# arduino_uno_shield.net
KiCad netlist of a schematic drawn in EAGLE
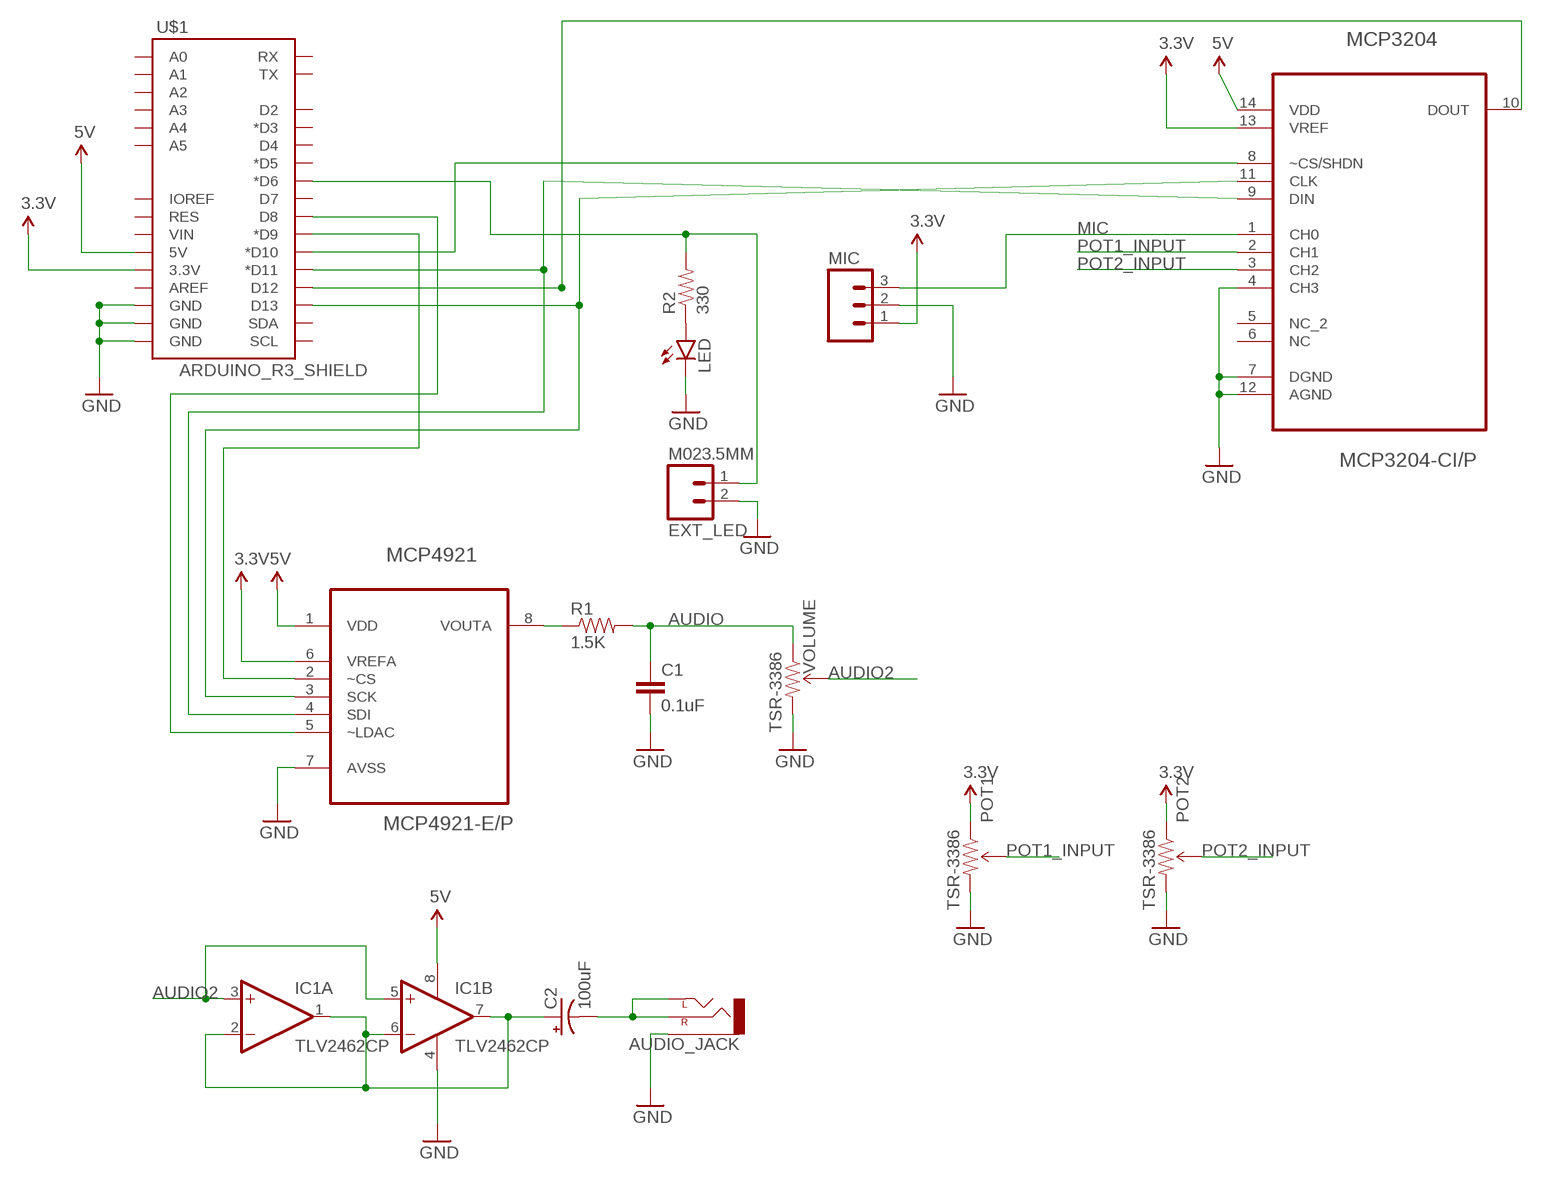
[diagram p0: schematic, sheet 1]

(export (version "E")
  (design (tool "Eeschema 10.0.6"))
  (components
    (comp (ref "AUDIO_JACK")
      (value "AUDIO-JACKPTH")
      (footprint "eagle-import:AUDIO-JACK")
      (libsource (lib "eagle-import") (part "AUDIO-JACKPTH"))
    )
    (comp (ref "C1")
      (value "0.1uF")
      (footprint "eagle-import:CAP-PTH-SMALL")
      (libsource (lib "eagle-import") (part "CAPPTH"))
    )
    (comp (ref "C2")
      (value "100uF")
      (footprint "eagle-import:CPOL-RADIAL-100UF-25V")
      (libsource (lib "eagle-import") (part "CAP_POLPTH1"))
    )
    (comp (ref "EXT_LED")
      (value "M023.5MM")
      (footprint "eagle-import:SCREWTERMINAL-3.5MM-2")
      (libsource (lib "eagle-import") (part "M023.5MM"))
    )
    (comp (ref "IC1")
      (value "TLV2462CP")
      (footprint "eagle-import:DIL08")
      (libsource (lib "eagle-import") (part "TL072P"))
    )
    (comp (ref "LED")
      (value "LED5MM")
      (footprint "eagle-import:LED5MM")
      (libsource (lib "eagle-import") (part "LED5MM"))
    )
    (comp (ref "MCP3204")
      (value "MCP3204-CI/P")
      (footprint "eagle-import:DIP254P762X432-14")
      (libsource (lib "eagle-import") (part "MCP3204-CI/P"))
    )
    (comp (ref "MCP4921")
      (value "MCP4921-E/P")
      (footprint "eagle-import:DIP254P762X432-8")
      (libsource (lib "eagle-import") (part "MCP4921-E/P"))
    )
    (comp (ref "MIC")
      (value "M03PTH")
      (footprint "eagle-import:1X03")
      (libsource (lib "eagle-import") (part "M03PTH"))
    )
    (comp (ref "POT1")
      (value "TSR-3386")
      (footprint "eagle-import:3386U")
      (libsource (lib "eagle-import") (part "TRIMPOT-PTH-KNOB"))
    )
    (comp (ref "POT2")
      (value "TSR-3386")
      (footprint "eagle-import:3386U")
      (libsource (lib "eagle-import") (part "TRIMPOT-PTH-KNOB"))
    )
    (comp (ref "R1")
      (value "1.5K")
      (footprint "eagle-import:AXIAL-0.4")
      (libsource (lib "eagle-import") (part "RESISTORPTH-1/4W"))
    )
    (comp (ref "R2")
      (value "330")
      (footprint "eagle-import:AXIAL-0.4")
      (libsource (lib "eagle-import") (part "RESISTORPTH-1/4W"))
    )
    (comp (ref "U$1")
      (value "ARDUINO_R3_SHIELD")
      (footprint "eagle-import:UNO_R3_SHIELD")
      (libsource (lib "eagle-import") (part "ARDUINO_R3_SHIELD"))
    )
    (comp (ref "VOLUME")
      (value "TSR-3386")
      (footprint "eagle-import:3386U")
      (libsource (lib "eagle-import") (part "TRIMPOT-PTH-KNOB"))
    )
  )
  (nets
    (net (code "1") (name "/AUDIO") (class "Default")
      (node (ref "C1") (pin "1") (pinfunction "1_1") (pintype "passive"))
      (node (ref "R1") (pin "P$2") (pinfunction "2_P$2") (pintype "passive"))
      (node (ref "VOLUME") (pin "1") (pinfunction "CCW_1") (pintype "passive"))
    )
    (net (code "2") (name "/AUDIO2") (class "Default")
      (node (ref "IC1") (pin "3") (pinfunction "+IN_3") (pintype "input"))
      (node (ref "IC1") (pin "5") (pinfunction "+IN_5") (pintype "input"))
      (node (ref "VOLUME") (pin "2") (pinfunction "WIPER_2") (pintype "passive"))
    )
    (net (code "3") (name "/MIC") (class "Default")
      (node (ref "MCP3204") (pin "1") (pinfunction "CH0_1") (pintype "input"))
      (node (ref "MIC") (pin "3") (pinfunction "3_3") (pintype "passive"))
    )
    (net (code "4") (name "/POT1_INPUT") (class "Default")
      (node (ref "MCP3204") (pin "2") (pinfunction "CH1_2") (pintype "input"))
      (node (ref "POT1") (pin "2") (pinfunction "WIPER_2") (pintype "passive"))
    )
    (net (code "5") (name "/POT2_INPUT") (class "Default")
      (node (ref "MCP3204") (pin "3") (pinfunction "CH2_3") (pintype "input"))
      (node (ref "POT2") (pin "2") (pinfunction "WIPER_2") (pintype "passive"))
    )
    (net (code "6") (name "3.3V") (class "Default")
      (node (ref "MCP3204") (pin "13") (pinfunction "VREF_13") (pintype "power_in"))
      (node (ref "MCP4921") (pin "6") (pinfunction "VREFA_6") (pintype "input"))
      (node (ref "MIC") (pin "1") (pinfunction "1_1") (pintype "passive"))
      (node (ref "POT1") (pin "1") (pinfunction "CCW_1") (pintype "passive"))
      (node (ref "POT2") (pin "1") (pinfunction "CCW_1") (pintype "passive"))
      (node (ref "U$1") (pin "3.3V") (pinfunction "3.3V_3.3V") (pintype "bidirectional"))
    )
    (net (code "7") (name "5V") (class "Default")
      (node (ref "IC1") (pin "8") (pinfunction "V+_8") (pintype "power_in"))
      (node (ref "MCP3204") (pin "14") (pinfunction "VDD_14") (pintype "power_in"))
      (node (ref "MCP4921") (pin "1") (pinfunction "VDD_1") (pintype "power_in"))
      (node (ref "U$1") (pin "5V") (pinfunction "5V_5V") (pintype "bidirectional"))
    )
    (net (code "8") (name "GND") (class "Default")
      (node (ref "AUDIO_JACK") (pin "SLEEVE") (pinfunction "SLEEVE_SLEEVE") (pintype "bidirectional"))
      (node (ref "C1") (pin "2") (pinfunction "2_2") (pintype "passive"))
      (node (ref "EXT_LED") (pin "2") (pinfunction "2_2") (pintype "passive"))
      (node (ref "IC1") (pin "4") (pinfunction "V-_4") (pintype "power_in"))
      (node (ref "LED") (pin "K") (pinfunction "C_K") (pintype "passive"))
      (node (ref "MCP3204") (pin "12") (pinfunction "AGND_12") (pintype "passive"))
      (node (ref "MCP3204") (pin "4") (pinfunction "CH3_4") (pintype "input"))
      (node (ref "MCP3204") (pin "7") (pinfunction "DGND_7") (pintype "passive"))
      (node (ref "MCP4921") (pin "7") (pinfunction "AVSS_7") (pintype "passive"))
      (node (ref "MIC") (pin "2") (pinfunction "2_2") (pintype "passive"))
      (node (ref "POT1") (pin "3") (pinfunction "CW_3") (pintype "passive"))
      (node (ref "POT2") (pin "3") (pinfunction "CW_3") (pintype "passive"))
      (node (ref "U$1") (pin "GND@0") (pinfunction "GND_GND@0") (pintype "bidirectional"))
      (node (ref "U$1") (pin "GND@1") (pinfunction "GND_GND@1") (pintype "bidirectional"))
      (node (ref "U$1") (pin "GND@2") (pinfunction "GND_GND@2") (pintype "bidirectional"))
      (node (ref "VOLUME") (pin "3") (pinfunction "CW_3") (pintype "passive"))
    )
    (net (code "9") (name "Net-(AUDIO_JACK-LEFT)") (class "Default")
      (node (ref "AUDIO_JACK") (pin "RING") (pinfunction "RIGHT_RING") (pintype "bidirectional"))
      (node (ref "AUDIO_JACK") (pin "TIP") (pinfunction "LEFT_TIP") (pintype "bidirectional"))
      (node (ref "C2") (pin "2") (pinfunction "-_2") (pintype "passive"))
    )
    (net (code "10") (name "Net-(C2-+)") (class "Default")
      (node (ref "C2") (pin "1") (pinfunction "+_1") (pintype "passive"))
      (node (ref "IC1") (pin "1") (pinfunction "OUT_1") (pintype "output"))
      (node (ref "IC1") (pin "2") (pinfunction "-IN_2") (pintype "input"))
      (node (ref "IC1") (pin "6") (pinfunction "-IN_6") (pintype "input"))
      (node (ref "IC1") (pin "7") (pinfunction "OUT_7") (pintype "output"))
    )
    (net (code "11") (name "Net-(MCP3204-CLK)") (class "Default")
      (node (ref "MCP3204") (pin "11") (pinfunction "CLK_11") (pintype "input"))
      (node (ref "MCP4921") (pin "3") (pinfunction "SCK_3") (pintype "input"))
      (node (ref "U$1") (pin "D13") (pinfunction "D13_D13") (pintype "bidirectional"))
    )
    (net (code "12") (name "Net-(MCP3204-DIN)") (class "Default")
      (node (ref "MCP3204") (pin "9") (pinfunction "DIN_9") (pintype "input"))
      (node (ref "MCP4921") (pin "4") (pinfunction "SDI_4") (pintype "input"))
      (node (ref "U$1") (pin "D11") (pinfunction "*D11_D11") (pintype "bidirectional"))
    )
    (net (code "13") (name "Net-(MCP3204-DOUT)") (class "Default")
      (node (ref "MCP3204") (pin "10") (pinfunction "DOUT_10") (pintype "output"))
      (node (ref "U$1") (pin "D12") (pinfunction "D12_D12") (pintype "bidirectional"))
    )
    (net (code "14") (name "Net-(MCP3204-~{CS{slash}SHDN})") (class "Default")
      (node (ref "MCP3204") (pin "8") (pinfunction "~{CS/SHDN}_8") (pintype "input"))
      (node (ref "U$1") (pin "D10") (pinfunction "*D10_D10") (pintype "bidirectional"))
    )
    (net (code "15") (name "Net-(MCP4921-VOUTA)") (class "Default")
      (node (ref "MCP4921") (pin "8") (pinfunction "VOUTA_8") (pintype "output"))
      (node (ref "R1") (pin "P$1") (pinfunction "1_P$1") (pintype "passive"))
    )
    (net (code "16") (name "Net-(MCP4921-~{CS})") (class "Default")
      (node (ref "MCP4921") (pin "2") (pinfunction "~{CS}_2") (pintype "input"))
      (node (ref "U$1") (pin "D9") (pinfunction "*D9_D9") (pintype "bidirectional"))
    )
    (net (code "17") (name "Net-(MCP4921-~{LDAC})") (class "Default")
      (node (ref "MCP4921") (pin "5") (pinfunction "~{LDAC}_5") (pintype "input"))
      (node (ref "U$1") (pin "D8") (pinfunction "D8_D8") (pintype "bidirectional"))
    )
    (net (code "18") (name "Net-(R2-1)") (class "Default")
      (node (ref "LED") (pin "A") (pinfunction "A_A") (pintype "passive"))
      (node (ref "R2") (pin "P$1") (pinfunction "1_P$1") (pintype "passive"))
    )
    (net (code "19") (name "Net-(R2-2)") (class "Default")
      (node (ref "EXT_LED") (pin "1") (pinfunction "1_1") (pintype "passive"))
      (node (ref "R2") (pin "P$2") (pinfunction "2_P$2") (pintype "passive"))
      (node (ref "U$1") (pin "D6") (pinfunction "*D6_D6") (pintype "bidirectional"))
    )
    (net (code "20") (name "unconnected-(MCP3204-NC-Pad6)") (class "Default")
      (node (ref "MCP3204") (pin "6") (pinfunction "NC_6") (pintype "no_connect"))
    )
    (net (code "21") (name "unconnected-(MCP3204-NC_2-Pad5)") (class "Default")
      (node (ref "MCP3204") (pin "5") (pinfunction "NC_2_5") (pintype "no_connect"))
    )
    (net (code "22") (name "unconnected-(U$1-*D3-PadD3)") (class "Default")
      (node (ref "U$1") (pin "D3") (pinfunction "*D3_D3") (pintype "bidirectional"))
    )
    (net (code "23") (name "unconnected-(U$1-*D5-PadD5)") (class "Default")
      (node (ref "U$1") (pin "D5") (pinfunction "*D5_D5") (pintype "bidirectional"))
    )
    (net (code "24") (name "unconnected-(U$1-PadA0)") (class "Default")
      (node (ref "U$1") (pin "A0") (pinfunction "A0_A0") (pintype "bidirectional"))
    )
    (net (code "25") (name "unconnected-(U$1-PadA1)") (class "Default")
      (node (ref "U$1") (pin "A1") (pinfunction "A1_A1") (pintype "bidirectional"))
    )
    (net (code "26") (name "unconnected-(U$1-PadA2)") (class "Default")
      (node (ref "U$1") (pin "A2") (pinfunction "A2_A2") (pintype "bidirectional"))
    )
    (net (code "27") (name "unconnected-(U$1-PadA3)") (class "Default")
      (node (ref "U$1") (pin "A3") (pinfunction "A3_A3") (pintype "bidirectional"))
    )
    (net (code "28") (name "unconnected-(U$1-PadA4)") (class "Default")
      (node (ref "U$1") (pin "A4") (pinfunction "A4_A4") (pintype "bidirectional"))
    )
    (net (code "29") (name "unconnected-(U$1-PadA5)") (class "Default")
      (node (ref "U$1") (pin "A5") (pinfunction "A5_A5") (pintype "bidirectional"))
    )
    (net (code "30") (name "unconnected-(U$1-PadAREF)") (class "Default")
      (node (ref "U$1") (pin "AREF") (pinfunction "AREF_AREF") (pintype "bidirectional"))
    )
    (net (code "31") (name "unconnected-(U$1-PadD2)") (class "Default")
      (node (ref "U$1") (pin "D2") (pinfunction "D2_D2") (pintype "bidirectional"))
    )
    (net (code "32") (name "unconnected-(U$1-PadD4)") (class "Default")
      (node (ref "U$1") (pin "D4") (pinfunction "D4_D4") (pintype "bidirectional"))
    )
    (net (code "33") (name "unconnected-(U$1-PadD7)") (class "Default")
      (node (ref "U$1") (pin "D7") (pinfunction "D7_D7") (pintype "bidirectional"))
    )
    (net (code "34") (name "unconnected-(U$1-PadIOREF)") (class "Default")
      (node (ref "U$1") (pin "IOREF") (pinfunction "IOREF_IOREF") (pintype "bidirectional"))
    )
    (net (code "35") (name "unconnected-(U$1-PadRES)") (class "Default")
      (node (ref "U$1") (pin "RES") (pinfunction "RES_RES") (pintype "bidirectional"))
    )
    (net (code "36") (name "unconnected-(U$1-PadRX)") (class "Default")
      (node (ref "U$1") (pin "RX") (pinfunction "RX_RX") (pintype "bidirectional"))
    )
    (net (code "37") (name "unconnected-(U$1-PadSCL)") (class "Default")
      (node (ref "U$1") (pin "SCL") (pinfunction "SCL_SCL") (pintype "bidirectional"))
    )
    (net (code "38") (name "unconnected-(U$1-PadSDA)") (class "Default")
      (node (ref "U$1") (pin "SDA") (pinfunction "SDA_SDA") (pintype "bidirectional"))
    )
    (net (code "39") (name "unconnected-(U$1-PadTX)") (class "Default")
      (node (ref "U$1") (pin "TX") (pinfunction "TX_TX") (pintype "bidirectional"))
    )
    (net (code "40") (name "unconnected-(U$1-PadVIN)") (class "Default")
      (node (ref "U$1") (pin "VIN") (pinfunction "VIN_VIN") (pintype "bidirectional"))
    )
  )
)
